# midi2cv.net
KiCad netlist of a schematic drawn in EAGLE
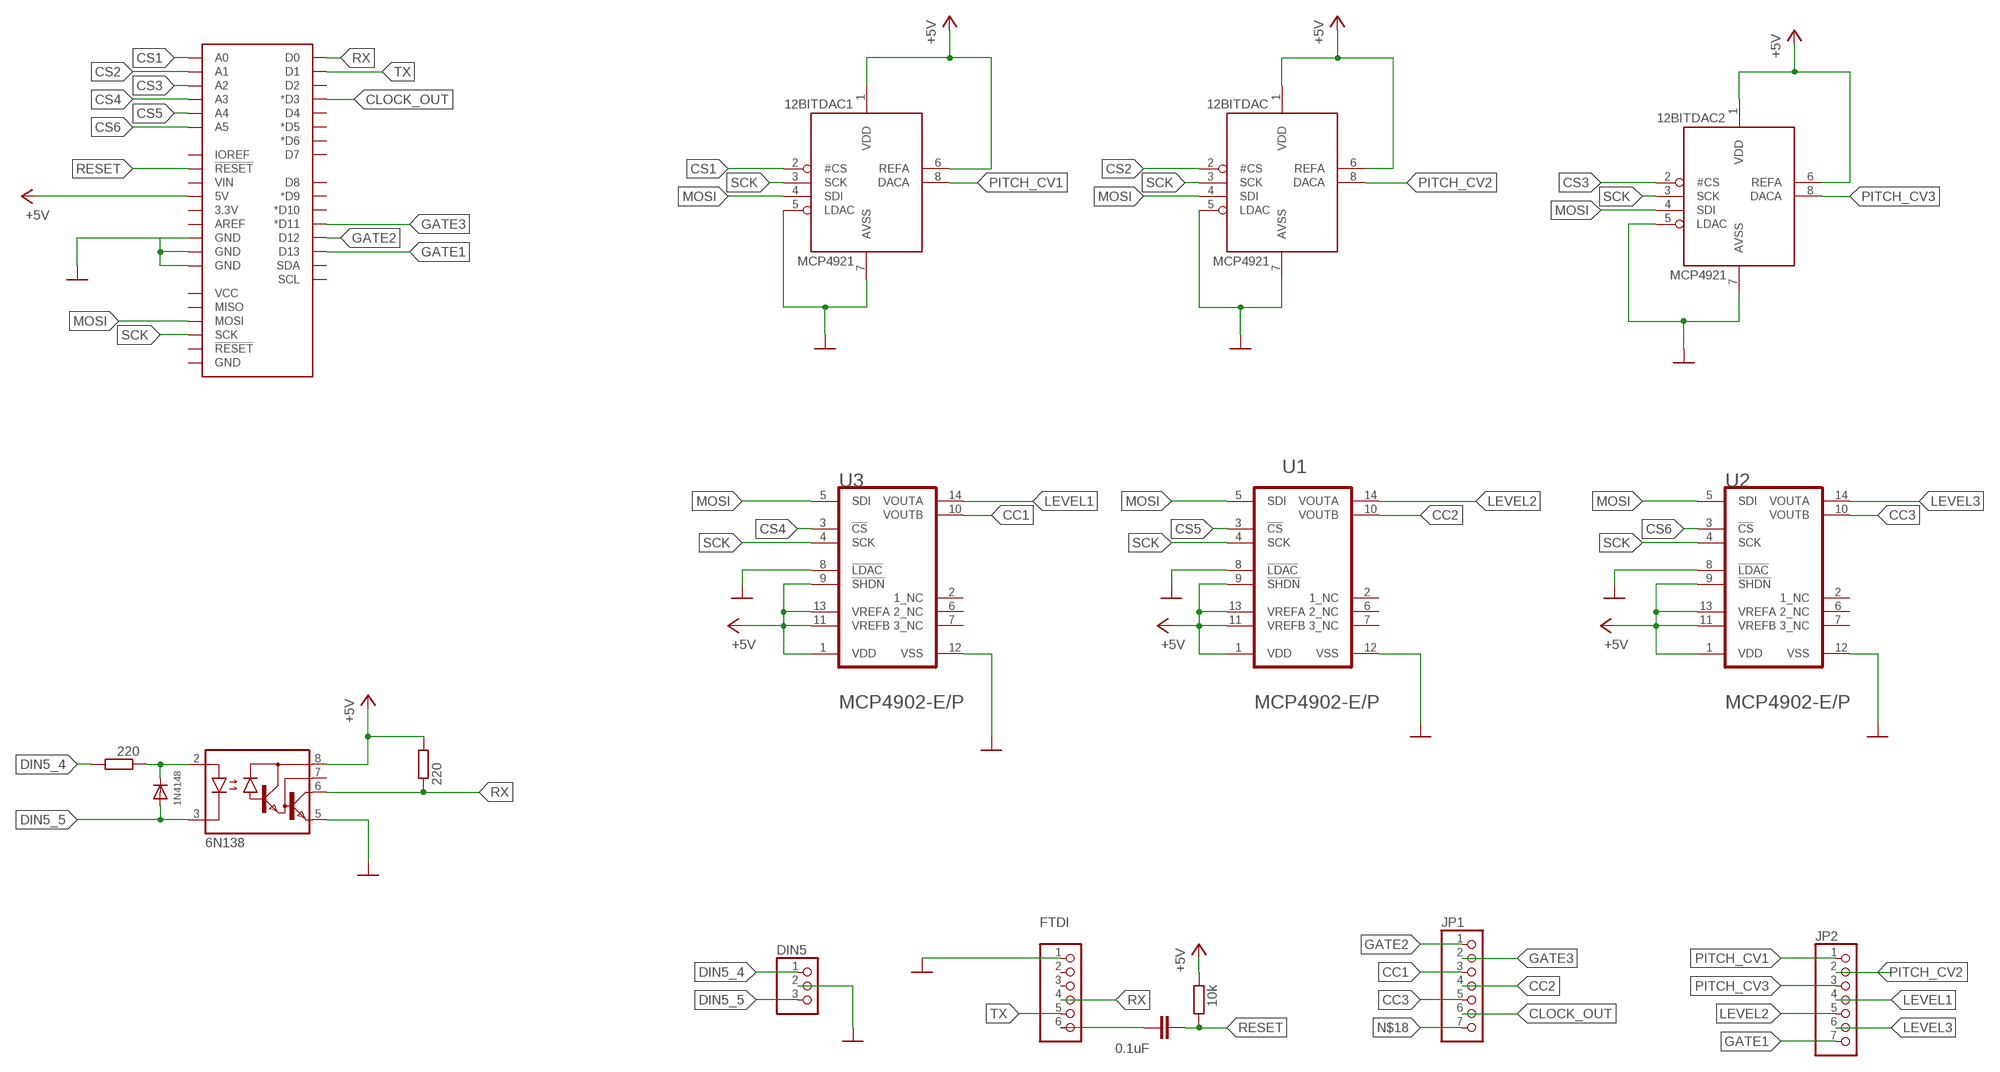
[diagram p0: schematic, sheet 1]

(export (version "E")
  (design (tool "Eeschema 10.0.6"))
  (components
    (comp (ref "12BITDAC")
      (value "MCP4921")
      (footprint "eagle-import:DIL08")
      (libsource (lib "eagle-import") (part "MCP4921"))
    )
    (comp (ref "12BITDAC1")
      (value "MCP4921")
      (footprint "eagle-import:DIL08")
      (libsource (lib "eagle-import") (part "MCP4921"))
    )
    (comp (ref "12BITDAC2")
      (value "MCP4921")
      (footprint "eagle-import:DIL08")
      (libsource (lib "eagle-import") (part "MCP4921"))
    )
    (comp (ref "B1")
      (value "ARDUINO_UNO_R3_SHIELD_ICSP-NO_LABELS")
      (footprint "eagle-import:UNO_R3_SHIELD_ICSP_NOLABELS")
      (libsource (lib "eagle-import") (part "ARDUINO_UNO_R3_SHIELD_ICSP-NO_LABELS"))
    )
    (comp (ref "C1")
      (value "0.1uF")
      (footprint "eagle-import:CAP-PTH-SMALL-KIT")
      (libsource (lib "eagle-import") (part "0.1UF-KIT-EZ-50V-20%"))
    )
    (comp (ref "D1")
      (value "1N4148")
      (footprint "eagle-import:DO-1N4148")
      (libsource (lib "eagle-import") (part "DIODEDO-1N4148"))
    )
    (comp (ref "DIN5")
      (value "PINHD-1X3")
      (footprint "eagle-import:1X03")
      (libsource (lib "eagle-import") (part "PINHD-1X3"))
    )
    (comp (ref "FTDI")
      (value "PINHD-1X6")
      (footprint "eagle-import:1X06")
      (libsource (lib "eagle-import") (part "PINHD-1X6"))
    )
    (comp (ref "JP1")
      (value "PINHD-1X7")
      (footprint "eagle-import:1X07")
      (libsource (lib "eagle-import") (part "PINHD-1X7"))
    )
    (comp (ref "JP2")
      (value "PINHD-1X7")
      (footprint "eagle-import:1X07")
      (libsource (lib "eagle-import") (part "PINHD-1X7"))
    )
    (comp (ref "OK1")
      (value "6N138")
      (footprint "eagle-import:DIL08")
      (fields (field (name "MF") "VISHAY/TELEFUNKEN"))
      (libsource (lib "eagle-import") (part "6N138"))
    )
    (comp (ref "R2")
      (value "220")
      (footprint "eagle-import:0207_10")
      (libsource (lib "eagle-import") (part "R-EU_0207/10"))
    )
    (comp (ref "R3")
      (value "220")
      (footprint "eagle-import:0207_10")
      (libsource (lib "eagle-import") (part "R-EU_0207/10"))
    )
    (comp (ref "R4")
      (value "10k")
      (footprint "eagle-import:0207_10")
      (libsource (lib "eagle-import") (part "R-EU_0207/10"))
    )
    (comp (ref "U1")
      (value "MICROCHIP_MCP4902-E-PMICROCHIP_MCP4902-E-P_0_0")
      (footprint "eagle-import:MICROCHIP_MCP4902-E-P_0")
      (fields (field (name "MF") "Microchip") (field (name "MPN") "MCP4902-E/P"))
      (libsource (lib "eagle-import") (part "MICROCHIP_MCP4902-E-PMICROCHIP_MCP4902-E-P_0_0"))
    )
    (comp (ref "U2")
      (value "MICROCHIP_MCP4902-E-PMICROCHIP_MCP4902-E-P_0_0")
      (footprint "eagle-import:MICROCHIP_MCP4902-E-P_0")
      (fields (field (name "MF") "Microchip") (field (name "MPN") "MCP4902-E/P"))
      (libsource (lib "eagle-import") (part "MICROCHIP_MCP4902-E-PMICROCHIP_MCP4902-E-P_0_0"))
    )
    (comp (ref "U3")
      (value "MICROCHIP_MCP4902-E-PMICROCHIP_MCP4902-E-P_0_0")
      (footprint "eagle-import:MICROCHIP_MCP4902-E-P_0")
      (fields (field (name "MF") "Microchip") (field (name "MPN") "MCP4902-E/P"))
      (libsource (lib "eagle-import") (part "MICROCHIP_MCP4902-E-PMICROCHIP_MCP4902-E-P_0_0"))
    )
  )
  (nets
    (net (code "1") (name "+5V") (class "Default")
      (node (ref "12BITDAC") (pin "1") (pinfunction "VDD_1") (pintype "power_in"))
      (node (ref "12BITDAC") (pin "6") (pinfunction "REFA_6") (pintype "input"))
      (node (ref "12BITDAC1") (pin "1") (pinfunction "VDD_1") (pintype "power_in"))
      (node (ref "12BITDAC1") (pin "6") (pinfunction "REFA_6") (pintype "input"))
      (node (ref "12BITDAC2") (pin "1") (pinfunction "VDD_1") (pintype "power_in"))
      (node (ref "12BITDAC2") (pin "6") (pinfunction "REFA_6") (pintype "input"))
      (node (ref "B1") (pin "5V") (pinfunction "5V_5V") (pintype "bidirectional"))
      (node (ref "OK1") (pin "8") (pinfunction "VCC_8") (pintype "passive"))
      (node (ref "R2") (pin "2") (pinfunction "2_2") (pintype "passive"))
      (node (ref "R4") (pin "2") (pinfunction "2_2") (pintype "passive"))
      (node (ref "U1") (pin "1") (pinfunction "VDD_1") (pintype "power_in"))
      (node (ref "U1") (pin "11") (pinfunction "VREFB_11") (pintype "input"))
      (node (ref "U1") (pin "13") (pinfunction "VREFA_13") (pintype "input"))
      (node (ref "U1") (pin "9") (pinfunction "~{SHDN}_9") (pintype "input"))
      (node (ref "U2") (pin "1") (pinfunction "VDD_1") (pintype "power_in"))
      (node (ref "U2") (pin "11") (pinfunction "VREFB_11") (pintype "input"))
      (node (ref "U2") (pin "13") (pinfunction "VREFA_13") (pintype "input"))
      (node (ref "U2") (pin "9") (pinfunction "~{SHDN}_9") (pintype "input"))
      (node (ref "U3") (pin "1") (pinfunction "VDD_1") (pintype "power_in"))
      (node (ref "U3") (pin "11") (pinfunction "VREFB_11") (pintype "input"))
      (node (ref "U3") (pin "13") (pinfunction "VREFA_13") (pintype "input"))
      (node (ref "U3") (pin "9") (pinfunction "~{SHDN}_9") (pintype "input"))
    )
    (net (code "2") (name "CC1") (class "Default")
      (node (ref "JP1") (pin "3") (pinfunction "3_3") (pintype "passive"))
      (node (ref "U3") (pin "10") (pinfunction "VOUTB_10") (pintype "output"))
    )
    (net (code "3") (name "CC2") (class "Default")
      (node (ref "JP1") (pin "4") (pinfunction "4_4") (pintype "passive"))
      (node (ref "U1") (pin "10") (pinfunction "VOUTB_10") (pintype "output"))
    )
    (net (code "4") (name "CC3") (class "Default")
      (node (ref "JP1") (pin "5") (pinfunction "5_5") (pintype "passive"))
      (node (ref "U2") (pin "10") (pinfunction "VOUTB_10") (pintype "output"))
    )
    (net (code "5") (name "CLOCK_OUT") (class "Default")
      (node (ref "B1") (pin "D3") (pinfunction "*D3_D3") (pintype "bidirectional"))
      (node (ref "JP1") (pin "6") (pinfunction "6_6") (pintype "passive"))
    )
    (net (code "6") (name "CS1") (class "Default")
      (node (ref "12BITDAC1") (pin "2") (pinfunction "#CS_2") (pintype "input"))
      (node (ref "B1") (pin "A0") (pinfunction "A0_A0") (pintype "bidirectional"))
    )
    (net (code "7") (name "CS2") (class "Default")
      (node (ref "12BITDAC") (pin "2") (pinfunction "#CS_2") (pintype "input"))
      (node (ref "B1") (pin "A1") (pinfunction "A1_A1") (pintype "bidirectional"))
    )
    (net (code "8") (name "CS3") (class "Default")
      (node (ref "12BITDAC2") (pin "2") (pinfunction "#CS_2") (pintype "input"))
      (node (ref "B1") (pin "A2") (pinfunction "A2_A2") (pintype "bidirectional"))
    )
    (net (code "9") (name "CS4") (class "Default")
      (node (ref "B1") (pin "A3") (pinfunction "A3_A3") (pintype "bidirectional"))
      (node (ref "U3") (pin "3") (pinfunction "~{CS}_3") (pintype "input"))
    )
    (net (code "10") (name "CS5") (class "Default")
      (node (ref "B1") (pin "A4") (pinfunction "A4_A4") (pintype "bidirectional"))
      (node (ref "U1") (pin "3") (pinfunction "~{CS}_3") (pintype "input"))
    )
    (net (code "11") (name "CS6") (class "Default")
      (node (ref "B1") (pin "A5") (pinfunction "A5_A5") (pintype "bidirectional"))
      (node (ref "U2") (pin "3") (pinfunction "~{CS}_3") (pintype "input"))
    )
    (net (code "12") (name "DIN5_4") (class "Default")
      (node (ref "DIN5") (pin "1") (pinfunction "1_1") (pintype "passive"))
      (node (ref "R3") (pin "2") (pinfunction "2_2") (pintype "passive"))
    )
    (net (code "13") (name "DIN5_5") (class "Default")
      (node (ref "D1") (pin "A") (pinfunction "A_A") (pintype "passive"))
      (node (ref "DIN5") (pin "3") (pinfunction "3_3") (pintype "passive"))
      (node (ref "OK1") (pin "3") (pinfunction "C_3") (pintype "passive"))
    )
    (net (code "14") (name "GATE1") (class "Default")
      (node (ref "B1") (pin "D13") (pinfunction "D13_D13") (pintype "bidirectional"))
      (node (ref "JP2") (pin "7") (pinfunction "7_7") (pintype "passive"))
    )
    (net (code "15") (name "GATE2") (class "Default")
      (node (ref "B1") (pin "D12") (pinfunction "D12_D12") (pintype "bidirectional"))
      (node (ref "JP1") (pin "1") (pinfunction "1_1") (pintype "passive"))
    )
    (net (code "16") (name "GATE3") (class "Default")
      (node (ref "B1") (pin "D11") (pinfunction "*D11_D11") (pintype "bidirectional"))
      (node (ref "JP1") (pin "2") (pinfunction "2_2") (pintype "passive"))
    )
    (net (code "17") (name "GND") (class "Default")
      (node (ref "12BITDAC") (pin "5") (pinfunction "LDAC_5") (pintype "input"))
      (node (ref "12BITDAC") (pin "7") (pinfunction "AVSS_7") (pintype "power_in"))
      (node (ref "12BITDAC1") (pin "5") (pinfunction "LDAC_5") (pintype "input"))
      (node (ref "12BITDAC1") (pin "7") (pinfunction "AVSS_7") (pintype "power_in"))
      (node (ref "12BITDAC2") (pin "5") (pinfunction "LDAC_5") (pintype "input"))
      (node (ref "12BITDAC2") (pin "7") (pinfunction "AVSS_7") (pintype "power_in"))
      (node (ref "B1") (pin "GND@0") (pinfunction "GND_GND@0") (pintype "bidirectional"))
      (node (ref "B1") (pin "GND@1") (pinfunction "GND_GND@1") (pintype "bidirectional"))
      (node (ref "B1") (pin "GND@2") (pinfunction "GND_GND@2") (pintype "bidirectional"))
      (node (ref "DIN5") (pin "2") (pinfunction "2_2") (pintype "passive"))
      (node (ref "FTDI") (pin "1") (pinfunction "1_1") (pintype "passive"))
      (node (ref "OK1") (pin "5") (pinfunction "GND_5") (pintype "passive"))
      (node (ref "U1") (pin "12") (pinfunction "VSS_12") (pintype "power_in"))
      (node (ref "U1") (pin "8") (pinfunction "~{LDAC}_8") (pintype "input"))
      (node (ref "U2") (pin "12") (pinfunction "VSS_12") (pintype "power_in"))
      (node (ref "U2") (pin "8") (pinfunction "~{LDAC}_8") (pintype "input"))
      (node (ref "U3") (pin "12") (pinfunction "VSS_12") (pintype "power_in"))
      (node (ref "U3") (pin "8") (pinfunction "~{LDAC}_8") (pintype "input"))
    )
    (net (code "18") (name "LEVEL1") (class "Default")
      (node (ref "JP2") (pin "4") (pinfunction "4_4") (pintype "passive"))
      (node (ref "U3") (pin "14") (pinfunction "VOUTA_14") (pintype "output"))
    )
    (net (code "19") (name "LEVEL2") (class "Default")
      (node (ref "JP2") (pin "5") (pinfunction "5_5") (pintype "passive"))
      (node (ref "U1") (pin "14") (pinfunction "VOUTA_14") (pintype "output"))
    )
    (net (code "20") (name "LEVEL3") (class "Default")
      (node (ref "JP2") (pin "6") (pinfunction "6_6") (pintype "passive"))
      (node (ref "U2") (pin "14") (pinfunction "VOUTA_14") (pintype "output"))
    )
    (net (code "21") (name "MOSI") (class "Default")
      (node (ref "12BITDAC") (pin "4") (pinfunction "SDI_4") (pintype "input"))
      (node (ref "12BITDAC1") (pin "4") (pinfunction "SDI_4") (pintype "input"))
      (node (ref "12BITDAC2") (pin "4") (pinfunction "SDI_4") (pintype "input"))
      (node (ref "B1") (pin "MOSI") (pinfunction "MOSI_MOSI") (pintype "bidirectional"))
      (node (ref "U1") (pin "5") (pinfunction "SDI_5") (pintype "input"))
      (node (ref "U2") (pin "5") (pinfunction "SDI_5") (pintype "input"))
      (node (ref "U3") (pin "5") (pinfunction "SDI_5") (pintype "input"))
    )
    (net (code "22") (name "N$18") (class "Default")
      (node (ref "JP1") (pin "7") (pinfunction "7_7") (pintype "passive"))
    )
    (net (code "23") (name "Net-(C1-Pad1)") (class "Default")
      (node (ref "C1") (pin "1") (pinfunction "1_1") (pintype "passive"))
      (node (ref "FTDI") (pin "6") (pinfunction "6_6") (pintype "passive"))
    )
    (net (code "24") (name "Net-(OK1-A)") (class "Default")
      (node (ref "D1") (pin "C") (pinfunction "C_C") (pintype "passive"))
      (node (ref "OK1") (pin "2") (pinfunction "A_2") (pintype "passive"))
      (node (ref "R3") (pin "1") (pinfunction "1_1") (pintype "passive"))
    )
    (net (code "25") (name "PITCH_CV1") (class "Default")
      (node (ref "12BITDAC1") (pin "8") (pinfunction "DACA_8") (pintype "output"))
      (node (ref "JP2") (pin "1") (pinfunction "1_1") (pintype "passive"))
    )
    (net (code "26") (name "PITCH_CV2") (class "Default")
      (node (ref "12BITDAC") (pin "8") (pinfunction "DACA_8") (pintype "output"))
      (node (ref "JP2") (pin "2") (pinfunction "2_2") (pintype "passive"))
    )
    (net (code "27") (name "PITCH_CV3") (class "Default")
      (node (ref "12BITDAC2") (pin "8") (pinfunction "DACA_8") (pintype "output"))
      (node (ref "JP2") (pin "3") (pinfunction "3_3") (pintype "passive"))
    )
    (net (code "28") (name "RESET") (class "Default")
      (node (ref "B1") (pin "RES") (pinfunction "~{RESET}_RES") (pintype "bidirectional"))
      (node (ref "C1") (pin "2") (pinfunction "2_2") (pintype "passive"))
      (node (ref "R4") (pin "1") (pinfunction "1_1") (pintype "passive"))
    )
    (net (code "29") (name "RX") (class "Default")
      (node (ref "B1") (pin "RX") (pinfunction "D0_RX") (pintype "bidirectional"))
      (node (ref "FTDI") (pin "4") (pinfunction "4_4") (pintype "passive"))
      (node (ref "OK1") (pin "6") (pinfunction "VO_6") (pintype "passive"))
      (node (ref "R2") (pin "1") (pinfunction "1_1") (pintype "passive"))
    )
    (net (code "30") (name "SCK") (class "Default")
      (node (ref "12BITDAC") (pin "3") (pinfunction "SCK_3") (pintype "input"))
      (node (ref "12BITDAC1") (pin "3") (pinfunction "SCK_3") (pintype "input"))
      (node (ref "12BITDAC2") (pin "3") (pinfunction "SCK_3") (pintype "input"))
      (node (ref "B1") (pin "SCK") (pinfunction "SCK_SCK") (pintype "bidirectional"))
      (node (ref "U1") (pin "4") (pinfunction "SCK_4") (pintype "input"))
      (node (ref "U2") (pin "4") (pinfunction "SCK_4") (pintype "input"))
      (node (ref "U3") (pin "4") (pinfunction "SCK_4") (pintype "input"))
    )
    (net (code "31") (name "TX") (class "Default")
      (node (ref "B1") (pin "TX") (pinfunction "D1_TX") (pintype "bidirectional"))
      (node (ref "FTDI") (pin "5") (pinfunction "5_5") (pintype "passive"))
    )
    (net (code "32") (name "unconnected-(B1-*D5-PadD5)") (class "Default")
      (node (ref "B1") (pin "D5") (pinfunction "*D5_D5") (pintype "bidirectional"))
    )
    (net (code "33") (name "unconnected-(B1-*D6-PadD6)") (class "Default")
      (node (ref "B1") (pin "D6") (pinfunction "*D6_D6") (pintype "bidirectional"))
    )
    (net (code "34") (name "unconnected-(B1-*D9-PadD9)") (class "Default")
      (node (ref "B1") (pin "D9") (pinfunction "*D9_D9") (pintype "bidirectional"))
    )
    (net (code "35") (name "unconnected-(B1-*D10-PadD10)") (class "Default")
      (node (ref "B1") (pin "D10") (pinfunction "*D10_D10") (pintype "bidirectional"))
    )
    (net (code "36") (name "unconnected-(B1-GND-PadGND_ICSP)") (class "Default")
      (node (ref "B1") (pin "GND_ICSP") (pinfunction "GND_GND_ICSP") (pintype "bidirectional"))
    )
    (net (code "37") (name "unconnected-(B1-Pad3.3V)") (class "Default")
      (node (ref "B1") (pin "3.3V") (pinfunction "3.3V_3.3V") (pintype "bidirectional"))
    )
    (net (code "38") (name "unconnected-(B1-PadAREF)") (class "Default")
      (node (ref "B1") (pin "AREF") (pinfunction "AREF_AREF") (pintype "bidirectional"))
    )
    (net (code "39") (name "unconnected-(B1-PadD2)") (class "Default")
      (node (ref "B1") (pin "D2") (pinfunction "D2_D2") (pintype "bidirectional"))
    )
    (net (code "40") (name "unconnected-(B1-PadD4)") (class "Default")
      (node (ref "B1") (pin "D4") (pinfunction "D4_D4") (pintype "bidirectional"))
    )
    (net (code "41") (name "unconnected-(B1-PadD7)") (class "Default")
      (node (ref "B1") (pin "D7") (pinfunction "D7_D7") (pintype "bidirectional"))
    )
    (net (code "42") (name "unconnected-(B1-PadD8)") (class "Default")
      (node (ref "B1") (pin "D8") (pinfunction "D8_D8") (pintype "bidirectional"))
    )
    (net (code "43") (name "unconnected-(B1-PadIOREF)") (class "Default")
      (node (ref "B1") (pin "IOREF") (pinfunction "IOREF_IOREF") (pintype "bidirectional"))
    )
    (net (code "44") (name "unconnected-(B1-PadMISO)") (class "Default")
      (node (ref "B1") (pin "MISO") (pinfunction "MISO_MISO") (pintype "bidirectional"))
    )
    (net (code "45") (name "unconnected-(B1-PadSCL)") (class "Default")
      (node (ref "B1") (pin "SCL") (pinfunction "SCL_SCL") (pintype "bidirectional"))
    )
    (net (code "46") (name "unconnected-(B1-PadSDA)") (class "Default")
      (node (ref "B1") (pin "SDA") (pinfunction "SDA_SDA") (pintype "bidirectional"))
    )
    (net (code "47") (name "unconnected-(B1-PadVIN)") (class "Default")
      (node (ref "B1") (pin "VIN") (pinfunction "VIN_VIN") (pintype "bidirectional"))
    )
    (net (code "48") (name "unconnected-(B1-VCC-Pad5V_ICSP)") (class "Default")
      (node (ref "B1") (pin "5V_ICSP") (pinfunction "VCC_5V_ICSP") (pintype "bidirectional"))
    )
    (net (code "49") (name "unconnected-(B1-~{RESET}-PadRST_ICSP)") (class "Default")
      (node (ref "B1") (pin "RST_ICSP") (pinfunction "~{RESET}_RST_ICSP") (pintype "bidirectional"))
    )
    (net (code "50") (name "unconnected-(FTDI-Pad2)") (class "Default")
      (node (ref "FTDI") (pin "2") (pinfunction "2_2") (pintype "passive"))
    )
    (net (code "51") (name "unconnected-(FTDI-Pad3)") (class "Default")
      (node (ref "FTDI") (pin "3") (pinfunction "3_3") (pintype "passive"))
    )
    (net (code "52") (name "unconnected-(OK1-VB-Pad7)") (class "Default")
      (node (ref "OK1") (pin "7") (pinfunction "VB_7") (pintype "passive"))
    )
    (net (code "53") (name "unconnected-(U1-1_NC-Pad2)") (class "Default")
      (node (ref "U1") (pin "2") (pinfunction "1_NC_2") (pintype "passive"))
    )
    (net (code "54") (name "unconnected-(U1-2_NC-Pad6)") (class "Default")
      (node (ref "U1") (pin "6") (pinfunction "2_NC_6") (pintype "passive"))
    )
    (net (code "55") (name "unconnected-(U1-3_NC-Pad7)") (class "Default")
      (node (ref "U1") (pin "7") (pinfunction "3_NC_7") (pintype "passive"))
    )
    (net (code "56") (name "unconnected-(U2-1_NC-Pad2)") (class "Default")
      (node (ref "U2") (pin "2") (pinfunction "1_NC_2") (pintype "passive"))
    )
    (net (code "57") (name "unconnected-(U2-2_NC-Pad6)") (class "Default")
      (node (ref "U2") (pin "6") (pinfunction "2_NC_6") (pintype "passive"))
    )
    (net (code "58") (name "unconnected-(U2-3_NC-Pad7)") (class "Default")
      (node (ref "U2") (pin "7") (pinfunction "3_NC_7") (pintype "passive"))
    )
    (net (code "59") (name "unconnected-(U3-1_NC-Pad2)") (class "Default")
      (node (ref "U3") (pin "2") (pinfunction "1_NC_2") (pintype "passive"))
    )
    (net (code "60") (name "unconnected-(U3-2_NC-Pad6)") (class "Default")
      (node (ref "U3") (pin "6") (pinfunction "2_NC_6") (pintype "passive"))
    )
    (net (code "61") (name "unconnected-(U3-3_NC-Pad7)") (class "Default")
      (node (ref "U3") (pin "7") (pinfunction "3_NC_7") (pintype "passive"))
    )
  )
)
